# schematic.net
KiCad netlist of a schematic drawn in EasyEDA
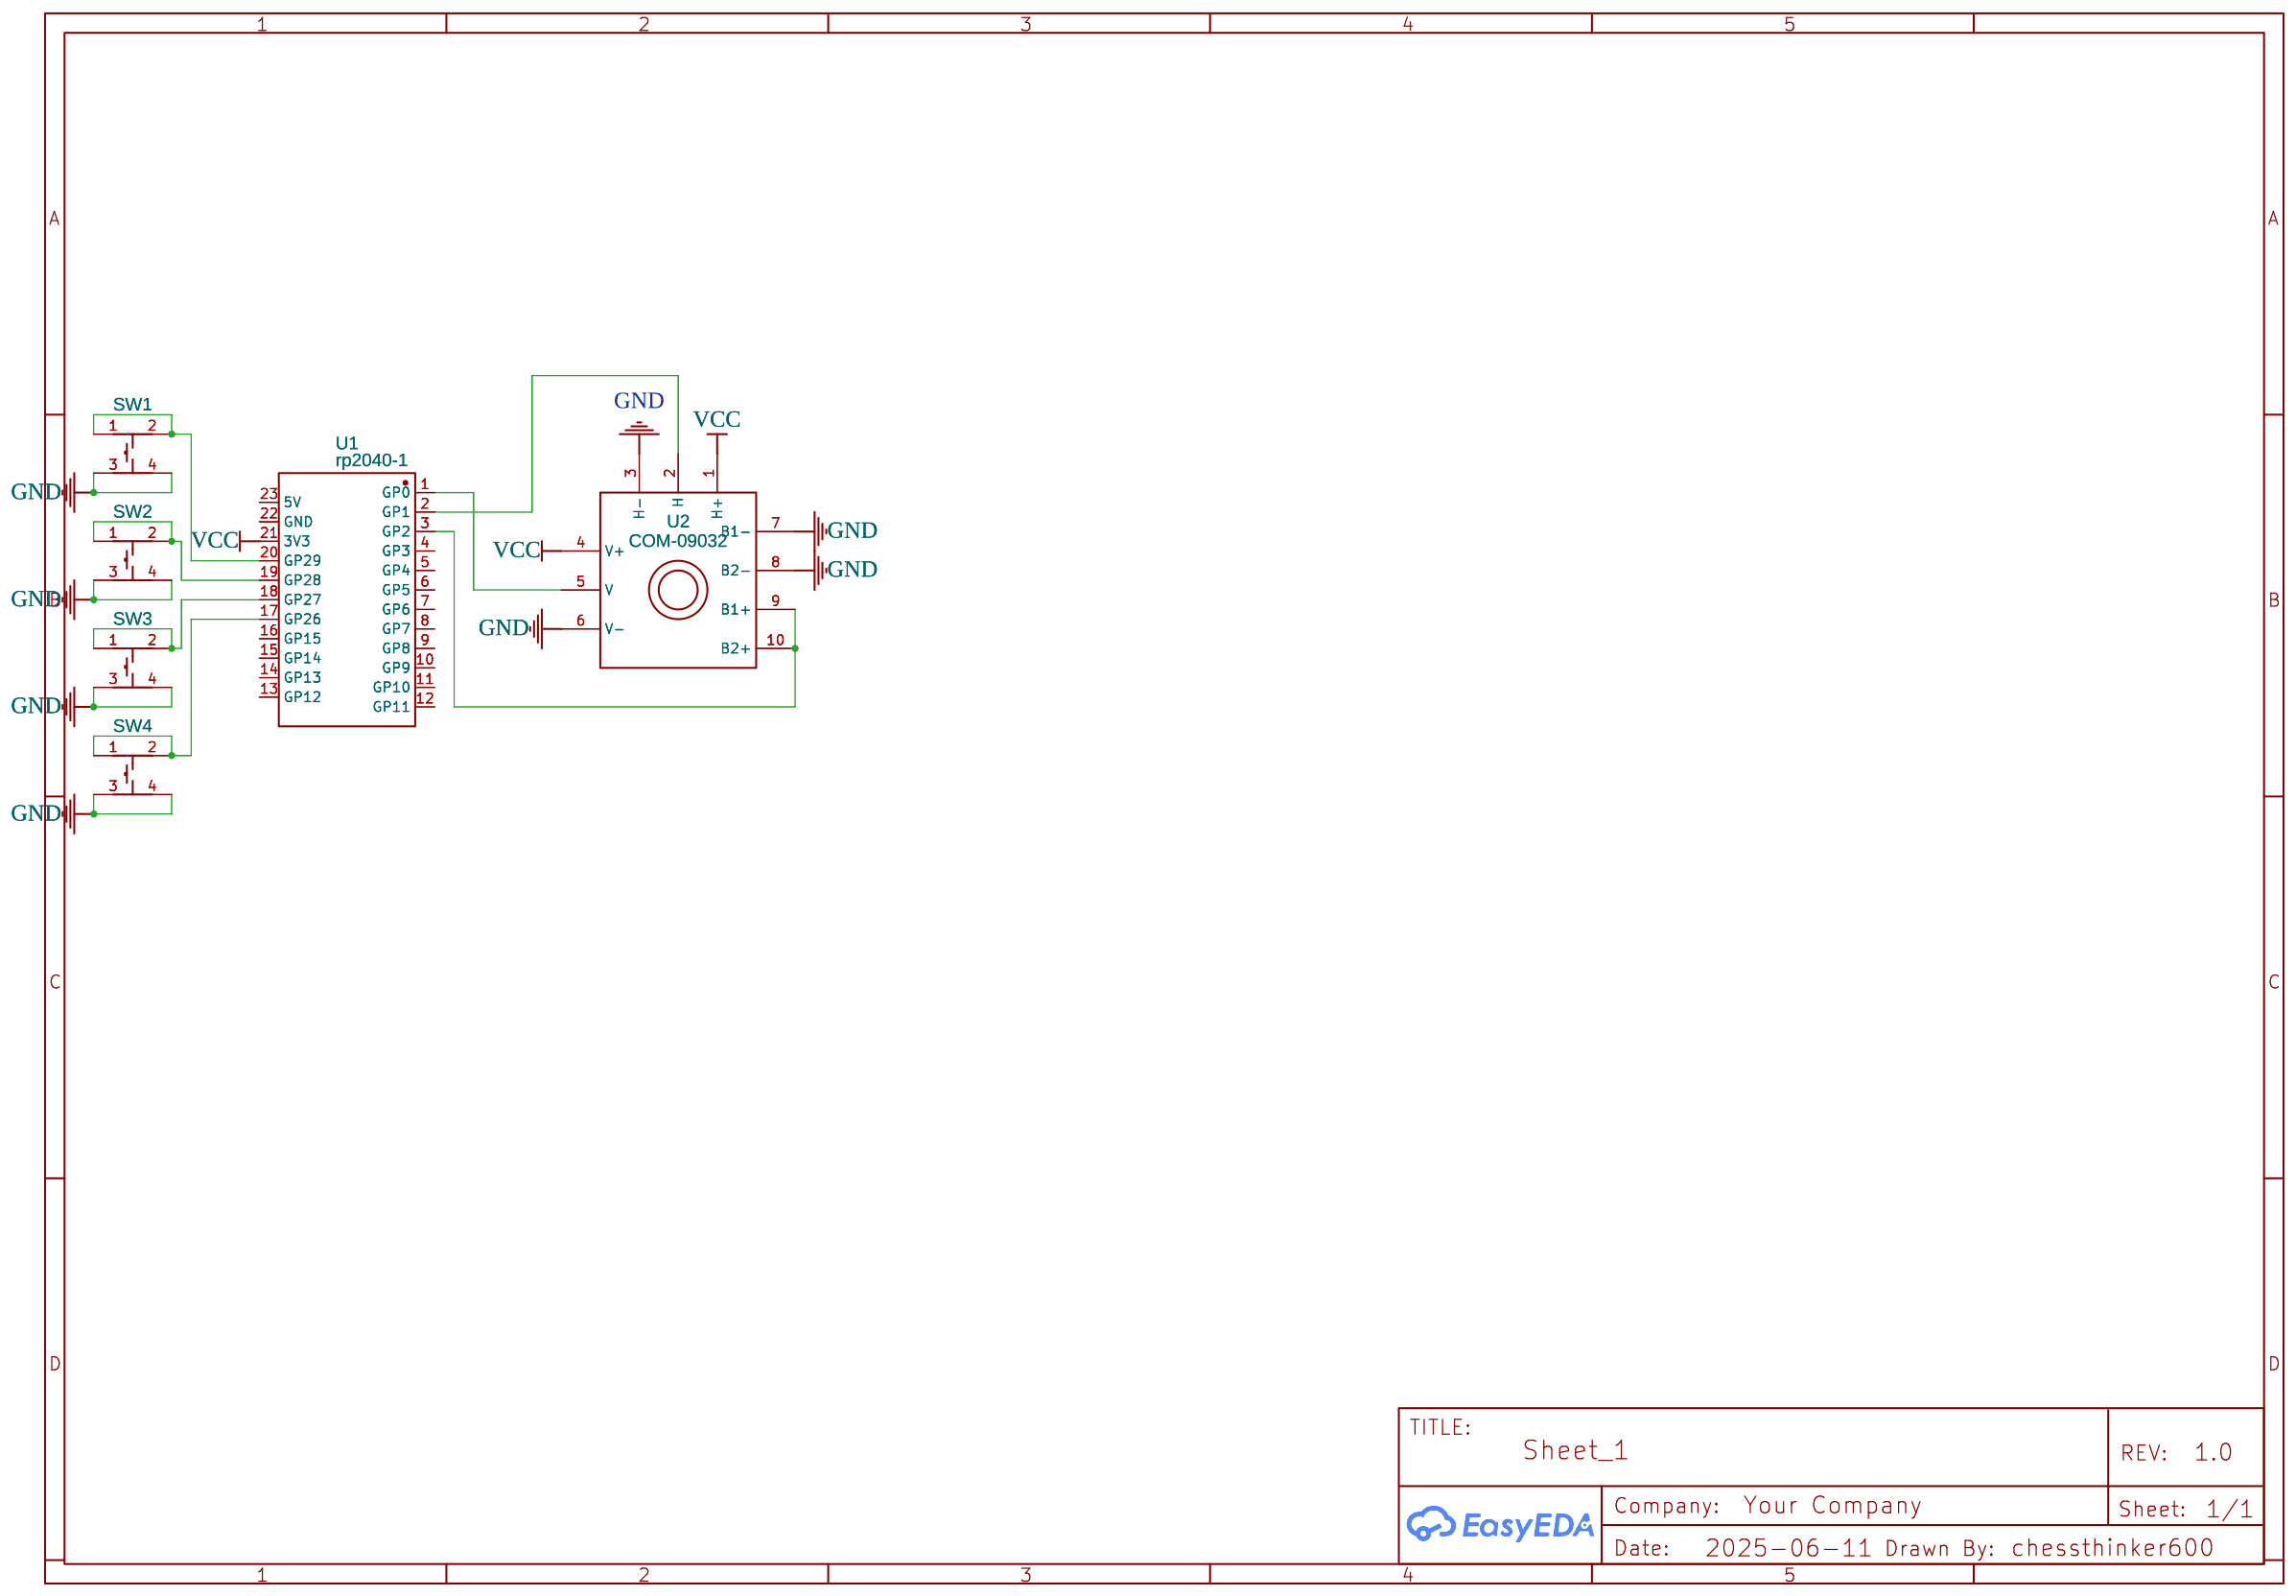
[diagram p0: schematic sheet]

(export (version "E")
  (design (tool "Eeschema 10.0.6"))
  (components
    (comp (ref "SW1")
      (value "TS-1095-A10B3-D1")
      (fields (field (name "Manufacturer") "Yuandi(元迪)"))
      (libsource (lib "") (part "TS-1095-A10B3-D1"))
    )
    (comp (ref "SW2")
      (value "TS-1095-A10B3-D1")
      (fields (field (name "Manufacturer") "Yuandi(元迪)"))
      (libsource (lib "") (part "TS-1095-A10B3-D1"))
    )
    (comp (ref "SW3")
      (value "TS-1095-A10B3-D1")
      (fields (field (name "Manufacturer") "Yuandi(元迪)"))
      (libsource (lib "") (part "TS-1095-A10B3-D1"))
    )
    (comp (ref "SW4")
      (value "TS-1095-A10B3-D1")
      (fields (field (name "Manufacturer") "Yuandi(元迪)"))
      (libsource (lib "") (part "TS-1095-A10B3-D1"))
    )
    (comp (ref "U1")
      (value "rp2040-1")
      (fields (field (name "Manufacturer Part") "RP2040-One") (field (name "Manufacturer") "Waveshare(微雪电子)"))
      (libsource (lib "") (part "RP2040-ONE COPY"))
    )
    (comp (ref "U2") (value "COM-09032") (libsource (lib "") (part "COM-09032")))
  )
  (nets
    (net (code "1") (name "GND") (class "Default")
      (node (ref "SW1") (pin "3") (pinfunction "3_3") (pintype "unspecified"))
      (node (ref "SW1") (pin "4") (pinfunction "4_4") (pintype "unspecified"))
      (node (ref "SW2") (pin "3") (pinfunction "3_3") (pintype "unspecified"))
      (node (ref "SW2") (pin "4") (pinfunction "4_4") (pintype "unspecified"))
      (node (ref "SW3") (pin "3") (pinfunction "3_3") (pintype "unspecified"))
      (node (ref "SW3") (pin "4") (pinfunction "4_4") (pintype "unspecified"))
      (node (ref "SW4") (pin "3") (pinfunction "3_3") (pintype "unspecified"))
      (node (ref "SW4") (pin "4") (pinfunction "4_4") (pintype "unspecified"))
      (node (ref "U2") (pin "3") (pinfunction "H-_3") (pintype "unspecified"))
      (node (ref "U2") (pin "6") (pinfunction "V-_6") (pintype "unspecified"))
      (node (ref "U2") (pin "7") (pinfunction "B1-_7") (pintype "unspecified"))
      (node (ref "U2") (pin "8") (pinfunction "B2-_8") (pintype "unspecified"))
    )
    (net (code "2") (name "Net-(U1-GP0)") (class "Default")
      (node (ref "U1") (pin "1") (pinfunction "GP0_1") (pintype "unspecified"))
      (node (ref "U2") (pin "5") (pinfunction "V_5") (pintype "unspecified"))
    )
    (net (code "3") (name "Net-(U1-GP1)") (class "Default")
      (node (ref "U1") (pin "2") (pinfunction "GP1_2") (pintype "unspecified"))
      (node (ref "U2") (pin "2") (pinfunction "H_2") (pintype "unspecified"))
    )
    (net (code "4") (name "Net-(U1-GP2)") (class "Default")
      (node (ref "U1") (pin "3") (pinfunction "GP2_3") (pintype "unspecified"))
      (node (ref "U2") (pin "10") (pinfunction "B2+_10") (pintype "unspecified"))
      (node (ref "U2") (pin "9") (pinfunction "B1+_9") (pintype "unspecified"))
    )
    (net (code "5") (name "Net-(U1-GP26)") (class "Default")
      (node (ref "SW4") (pin "1") (pinfunction "1_1") (pintype "unspecified"))
      (node (ref "SW4") (pin "2") (pinfunction "2_2") (pintype "unspecified"))
      (node (ref "U1") (pin "17") (pinfunction "GP26_17") (pintype "unspecified"))
    )
    (net (code "6") (name "Net-(U1-GP27)") (class "Default")
      (node (ref "SW3") (pin "1") (pinfunction "1_1") (pintype "unspecified"))
      (node (ref "SW3") (pin "2") (pinfunction "2_2") (pintype "unspecified"))
      (node (ref "U1") (pin "18") (pinfunction "GP27_18") (pintype "unspecified"))
    )
    (net (code "7") (name "Net-(U1-GP28)") (class "Default")
      (node (ref "SW2") (pin "1") (pinfunction "1_1") (pintype "unspecified"))
      (node (ref "SW2") (pin "2") (pinfunction "2_2") (pintype "unspecified"))
      (node (ref "U1") (pin "19") (pinfunction "GP28_19") (pintype "unspecified"))
    )
    (net (code "8") (name "Net-(U1-GP29)") (class "Default")
      (node (ref "SW1") (pin "1") (pinfunction "1_1") (pintype "unspecified"))
      (node (ref "SW1") (pin "2") (pinfunction "2_2") (pintype "unspecified"))
      (node (ref "U1") (pin "20") (pinfunction "GP29_20") (pintype "unspecified"))
    )
    (net (code "9") (name "VCC") (class "Default")
      (node (ref "U1") (pin "21") (pinfunction "3V3_21") (pintype "unspecified"))
      (node (ref "U2") (pin "1") (pinfunction "H+_1") (pintype "unspecified"))
      (node (ref "U2") (pin "4") (pinfunction "V+_4") (pintype "unspecified"))
    )
    (net (code "10") (name "unconnected-(U1-5V-Pad23)") (class "Default")
      (node (ref "U1") (pin "23") (pinfunction "5V_23") (pintype "unspecified"))
    )
    (net (code "11") (name "unconnected-(U1-GND-Pad22)") (class "Default")
      (node (ref "U1") (pin "22") (pinfunction "GND_22") (pintype "unspecified"))
    )
    (net (code "12") (name "unconnected-(U1-GP3-Pad4)") (class "Default")
      (node (ref "U1") (pin "4") (pinfunction "GP3_4") (pintype "unspecified"))
    )
    (net (code "13") (name "unconnected-(U1-GP4-Pad5)") (class "Default")
      (node (ref "U1") (pin "5") (pinfunction "GP4_5") (pintype "unspecified"))
    )
    (net (code "14") (name "unconnected-(U1-GP5-Pad6)") (class "Default")
      (node (ref "U1") (pin "6") (pinfunction "GP5_6") (pintype "unspecified"))
    )
    (net (code "15") (name "unconnected-(U1-GP6-Pad7)") (class "Default")
      (node (ref "U1") (pin "7") (pinfunction "GP6_7") (pintype "unspecified"))
    )
    (net (code "16") (name "unconnected-(U1-GP7-Pad8)") (class "Default")
      (node (ref "U1") (pin "8") (pinfunction "GP7_8") (pintype "unspecified"))
    )
    (net (code "17") (name "unconnected-(U1-GP8-Pad9)") (class "Default")
      (node (ref "U1") (pin "9") (pinfunction "GP8_9") (pintype "unspecified"))
    )
    (net (code "18") (name "unconnected-(U1-GP9-Pad10)") (class "Default")
      (node (ref "U1") (pin "10") (pinfunction "GP9_10") (pintype "unspecified"))
    )
    (net (code "19") (name "unconnected-(U1-GP10-Pad11)") (class "Default")
      (node (ref "U1") (pin "11") (pinfunction "GP10_11") (pintype "unspecified"))
    )
    (net (code "20") (name "unconnected-(U1-GP11-Pad12)") (class "Default")
      (node (ref "U1") (pin "12") (pinfunction "GP11_12") (pintype "unspecified"))
    )
    (net (code "21") (name "unconnected-(U1-GP12-Pad13)") (class "Default")
      (node (ref "U1") (pin "13") (pinfunction "GP12_13") (pintype "unspecified"))
    )
    (net (code "22") (name "unconnected-(U1-GP13-Pad14)") (class "Default")
      (node (ref "U1") (pin "14") (pinfunction "GP13_14") (pintype "unspecified"))
    )
    (net (code "23") (name "unconnected-(U1-GP14-Pad15)") (class "Default")
      (node (ref "U1") (pin "15") (pinfunction "GP14_15") (pintype "unspecified"))
    )
    (net (code "24") (name "unconnected-(U1-GP15-Pad16)") (class "Default")
      (node (ref "U1") (pin "16") (pinfunction "GP15_16") (pintype "unspecified"))
    )
  )
)
